# level_shifter.net
KiCad netlist of a schematic drawn in Altium Designer
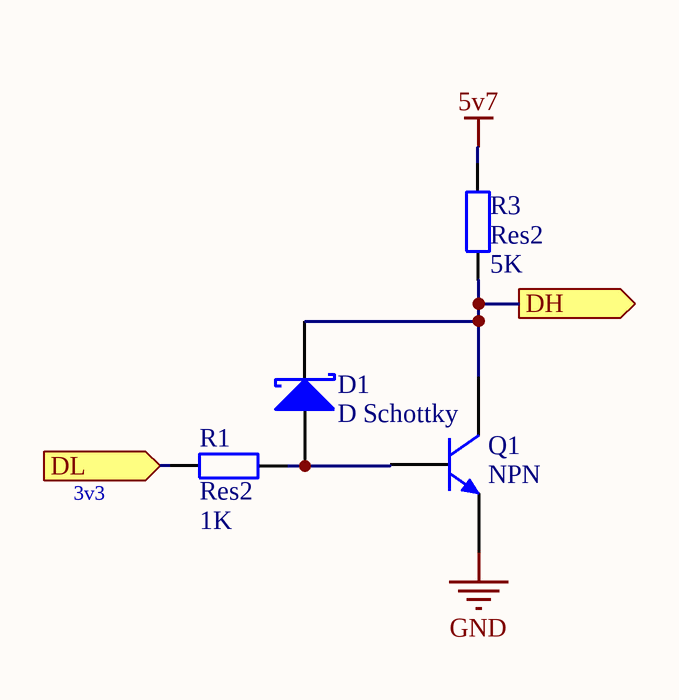
[diagram p0: level_shifter.SchDoc]

(export (version "E")
  (design (tool "Eeschema 10.0.6"))
  (components
    (comp (ref "D1")
      (value "D Schottky")
      (footprint "SMB")
      (description "Schottky Diode")
      (fields (field (name "PUBLISHER") "Altium Limited"))
      (libsource (lib "Miscellaneous Devices") (part "D Schottky"))
    )
    (comp (ref "Q1")
      (value "NPN")
      (footprint "TO-226-AA")
      (description "NPN Bipolar Transistor")
      (fields (field (name "PUBLISHER") "Altium Limited"))
      (libsource (lib "Miscellaneous Devices") (part "NPN"))
    )
    (comp (ref "R1")
      (value "Res2")
      (footprint "AXIAL-0.4")
      (description "Resistor")
      (fields (field (name "ALTIUM_VALUE") "1K") (field (name "PUBLISHER") "Altium Limited"))
      (libsource (lib "Miscellaneous Devices") (part "Res2"))
    )
    (comp (ref "R3")
      (value "Res2")
      (footprint "AXIAL-0.4")
      (description "Resistor")
      (fields (field (name "ALTIUM_VALUE") "5K") (field (name "PUBLISHER") "Altium Limited"))
      (libsource (lib "") (part "Res2_1"))
    )
  )
  (nets
    (net (code "1") (name "/DH") (class "Default")
      (node (ref "D1") (pin "2") (pinfunction "K_2") (pintype "passive"))
      (node (ref "Q1") (pin "1") (pinfunction "C_1") (pintype "passive"))
      (node (ref "R3") (pin "1") (pinfunction "1_1") (pintype "passive"))
    )
    (net (code "2") (name "/DL") (class "Default")
      (node (ref "R1") (pin "1") (pinfunction "1_1") (pintype "passive"))
    )
    (net (code "3") (name "5v7") (class "Default")
      (node (ref "R3") (pin "2") (pinfunction "2_2") (pintype "passive"))
    )
    (net (code "4") (name "GND") (class "Default")
      (node (ref "Q1") (pin "3") (pinfunction "E_3") (pintype "passive"))
    )
    (net (code "5") (name "Net-(D1-A)") (class "Default")
      (node (ref "D1") (pin "1") (pinfunction "A_1") (pintype "passive"))
      (node (ref "Q1") (pin "2") (pinfunction "B_2") (pintype "passive"))
      (node (ref "R1") (pin "2") (pinfunction "2_2") (pintype "passive"))
    )
  )
)
